# NixieClockControllerWemos.net
KiCad netlist of a schematic drawn in EAGLE
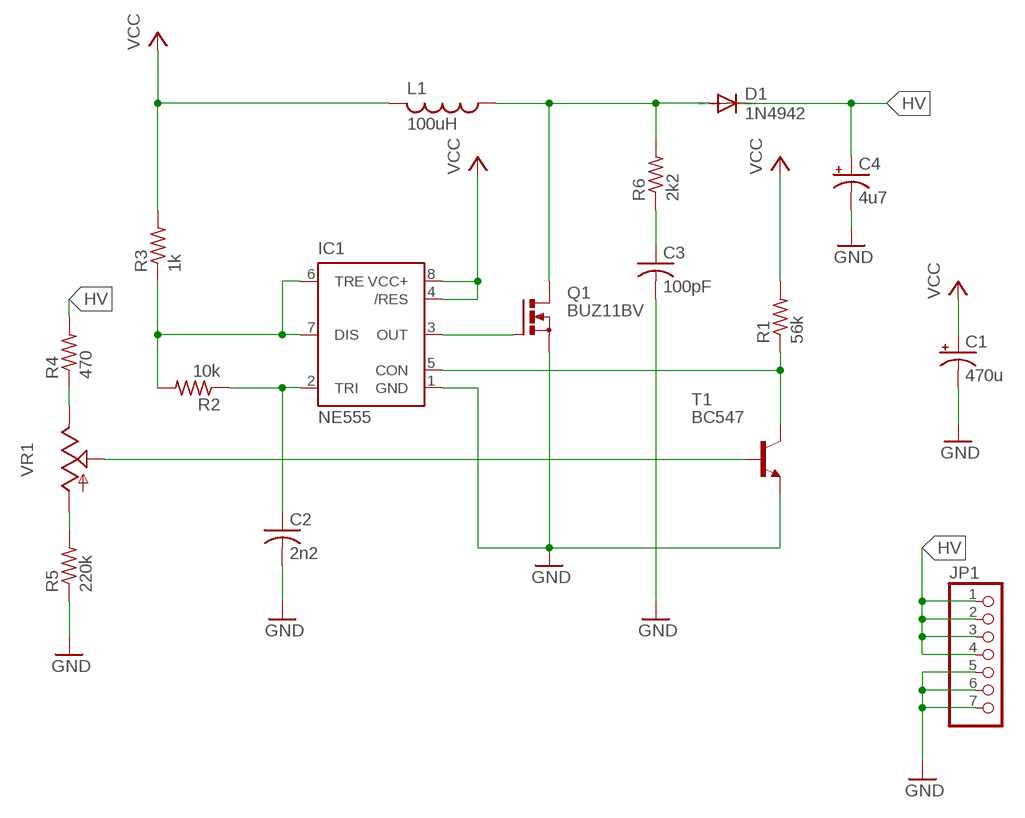
[diagram p0: schematic, sheet 1]
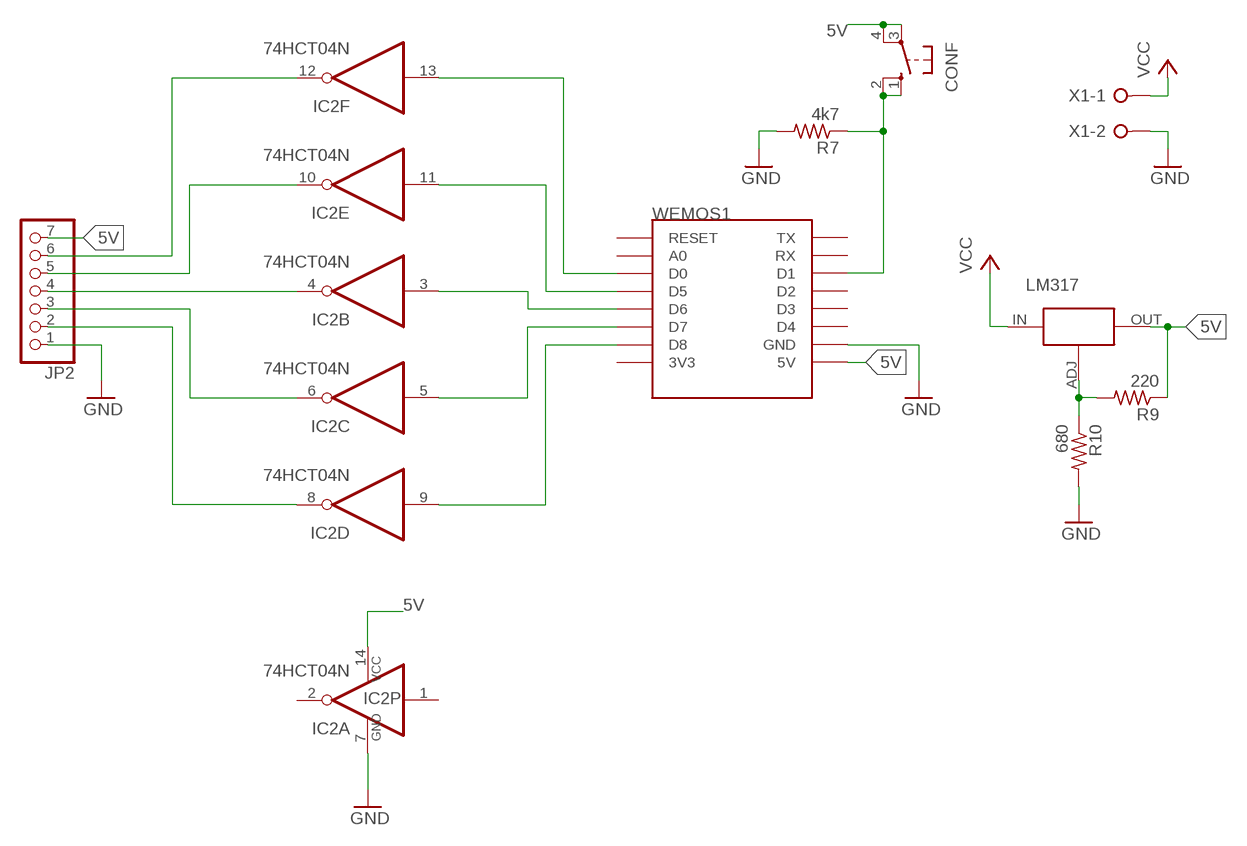
[diagram p1: schematic, sheet 2]

(export (version "E")
  (design (tool "Eeschema 10.0.6"))
  (components
    (comp (ref "C1")
      (value "470u")
      (footprint "eagle-import:E5-13")
      (libsource (lib "eagle-import") (part "CPOL-USE5-13"))
    )
    (comp (ref "C2")
      (value "2n2")
      (footprint "eagle-import:C050-025X075")
      (libsource (lib "eagle-import") (part "C-US050-025X075"))
    )
    (comp (ref "C3")
      (value "100pF")
      (footprint "eagle-import:C050-025X075")
      (libsource (lib "eagle-import") (part "C-US050-025X075"))
    )
    (comp (ref "C4")
      (value "4u7")
      (footprint "eagle-import:E3,5-8")
      (libsource (lib "eagle-import") (part "CPOL-USE3.5-8"))
    )
    (comp (ref "D1")
      (value "1N4942")
      (footprint "eagle-import:DO41-10")
      (libsource (lib "eagle-import") (part "1N4942"))
    )
    (comp (ref "IC1")
      (value "NE555")
      (footprint "eagle-import:DIL-08")
      (fields (field (name "MF") "Arrow Electronics") (field (name "MPN") "NE555N"))
      (libsource (lib "eagle-import") (part "NE555"))
    )
    (comp (ref "JP1")
      (value "PINHD-1X7")
      (footprint "eagle-import:1X07")
      (libsource (lib "eagle-import") (part "PINHD-1X7"))
    )
    (comp (ref "L1")
      (value "100uH")
      (footprint "eagle-import:RLB0914")
      (libsource (lib "eagle-import") (part "L-US"))
    )
    (comp (ref "Q1")
      (value "BUZ11BV")
      (footprint "eagle-import:TO220BV")
      (libsource (lib "eagle-import") (part "BUZ11BV"))
    )
    (comp (ref "R1")
      (value "56k")
      (footprint "eagle-import:0207_10")
      (libsource (lib "eagle-import") (part "R-US_0207/10"))
    )
    (comp (ref "R2")
      (value "10k")
      (footprint "eagle-import:0207_10")
      (libsource (lib "eagle-import") (part "R-US_0207/10"))
    )
    (comp (ref "R3")
      (value "1k")
      (footprint "eagle-import:0207_10")
      (libsource (lib "eagle-import") (part "R-US_0207/10"))
    )
    (comp (ref "R4")
      (value "470")
      (footprint "eagle-import:0207_10")
      (libsource (lib "eagle-import") (part "R-US_0207/10"))
    )
    (comp (ref "R5")
      (value "220k")
      (footprint "eagle-import:0207_10")
      (libsource (lib "eagle-import") (part "R-US_0207/10"))
    )
    (comp (ref "R6")
      (value "2k2")
      (footprint "eagle-import:0207_10")
      (libsource (lib "eagle-import") (part "R-US_0207/10"))
    )
    (comp (ref "T1")
      (value "BC547")
      (footprint "eagle-import:TO92")
      (libsource (lib "eagle-import") (part "BC547"))
    )
    (comp (ref "VR1")
      (value "TRIM_US-B25P")
      (footprint "eagle-import:B25P")
      (libsource (lib "eagle-import") (part "TRIM_US-B25P"))
    )
    (comp (ref "CONF")
      (value "10-XX")
      (footprint "eagle-import:B3F-10XX")
      (fields (field (name "MPN") "B3F-1000"))
      (libsource (lib "eagle-import") (part "10-XX"))
    )
    (comp (ref "IC2")
      (value "74HCT04N")
      (footprint "eagle-import:DIL14")
      (libsource (lib "eagle-import") (part "7404NHCT"))
    )
    (comp (ref "JP2")
      (value "PINHD-1X7")
      (footprint "eagle-import:1X07")
      (libsource (lib "eagle-import") (part "PINHD-1X7"))
    )
    (comp (ref "R7")
      (value "4k7")
      (footprint "eagle-import:0207_10")
      (libsource (lib "eagle-import") (part "R-US_0207/10"))
    )
    (comp (ref "R9")
      (value "220")
      (footprint "eagle-import:0207_10")
      (libsource (lib "eagle-import") (part "R-US_0207/10"))
    )
    (comp (ref "R10")
      (value "680")
      (footprint "eagle-import:0207_10")
      (libsource (lib "eagle-import") (part "R-US_0207/10"))
    )
    (comp (ref "U$3")
      (value "LM317-TO220")
      (footprint "eagle-import:LM317-TO220AV")
      (libsource (lib "eagle-import") (part "LM317-TO220"))
    )
    (comp (ref "WEMOS1")
      (value "WEMOS-D1-MINI")
      (footprint "eagle-import:WEMOS-D1-MINI")
      (libsource (lib "eagle-import") (part "WEMOS-D1-MINI"))
    )
    (comp (ref "X1")
      (value "W237-02P")
      (footprint "eagle-import:W237-132")
      (libsource (lib "eagle-import") (part "W237-02P"))
    )
  )
  (nets
    (net (code "1") (name "5V") (class "Default")
      (node (ref "CONF") (pin "3") (pinfunction "P_3") (pintype "passive"))
      (node (ref "CONF") (pin "4") (pinfunction "P1_4") (pintype "passive"))
      (node (ref "IC2") (pin "14") (pinfunction "VCC_14") (pintype "power_in"))
      (node (ref "JP2") (pin "7") (pinfunction "7_7") (pintype "passive"))
      (node (ref "R9") (pin "1") (pinfunction "1_1") (pintype "passive"))
      (node (ref "U$3") (pin "OUT") (pinfunction "VO_OUT") (pintype "output"))
      (node (ref "WEMOS1") (pin "5V") (pinfunction "5V_5V") (pintype "bidirectional"))
    )
    (net (code "2") (name "GND") (class "Default")
      (node (ref "C1") (pin "-") (pinfunction "-_-") (pintype "passive"))
      (node (ref "C2") (pin "2") (pinfunction "2_2") (pintype "passive"))
      (node (ref "C3") (pin "2") (pinfunction "2_2") (pintype "passive"))
      (node (ref "C4") (pin "-") (pinfunction "-_-") (pintype "passive"))
      (node (ref "IC1") (pin "1") (pinfunction "GND_1") (pintype "power_in"))
      (node (ref "IC2") (pin "7") (pinfunction "GND_7") (pintype "power_in"))
      (node (ref "JP1") (pin "5") (pinfunction "5_5") (pintype "passive"))
      (node (ref "JP1") (pin "6") (pinfunction "6_6") (pintype "passive"))
      (node (ref "JP1") (pin "7") (pinfunction "7_7") (pintype "passive"))
      (node (ref "JP2") (pin "1") (pinfunction "1_1") (pintype "passive"))
      (node (ref "Q1") (pin "S") (pinfunction "S_S") (pintype "passive"))
      (node (ref "R10") (pin "2") (pinfunction "2_2") (pintype "passive"))
      (node (ref "R5") (pin "1") (pinfunction "1_1") (pintype "passive"))
      (node (ref "R7") (pin "2") (pinfunction "2_2") (pintype "passive"))
      (node (ref "T1") (pin "1") (pinfunction "E_1") (pintype "passive"))
      (node (ref "WEMOS1") (pin "GND") (pinfunction "GND_GND") (pintype "bidirectional"))
      (node (ref "X1") (pin "2") (pinfunction "KL_2") (pintype "passive"))
    )
    (net (code "3") (name "HV") (class "Default")
      (node (ref "C4") (pin "+") (pinfunction "+_+") (pintype "passive"))
      (node (ref "D1") (pin "C") (pinfunction "C_C") (pintype "passive"))
      (node (ref "JP1") (pin "1") (pinfunction "1_1") (pintype "passive"))
      (node (ref "JP1") (pin "2") (pinfunction "2_2") (pintype "passive"))
      (node (ref "JP1") (pin "3") (pinfunction "3_3") (pintype "passive"))
      (node (ref "JP1") (pin "4") (pinfunction "4_4") (pintype "passive"))
      (node (ref "R4") (pin "2") (pinfunction "2_2") (pintype "passive"))
    )
    (net (code "4") (name "Net-(C3-Pad1)") (class "Default")
      (node (ref "C3") (pin "1") (pinfunction "1_1") (pintype "passive"))
      (node (ref "R6") (pin "1") (pinfunction "1_1") (pintype "passive"))
    )
    (net (code "5") (name "Net-(CONF-S)") (class "Default")
      (node (ref "CONF") (pin "1") (pinfunction "S_1") (pintype "passive"))
      (node (ref "CONF") (pin "2") (pinfunction "S1_2") (pintype "passive"))
      (node (ref "R7") (pin "1") (pinfunction "1_1") (pintype "passive"))
      (node (ref "WEMOS1") (pin "D1") (pinfunction "D1_D1") (pintype "bidirectional"))
    )
    (net (code "6") (name "Net-(D1-PadA)") (class "Default")
      (node (ref "D1") (pin "A") (pinfunction "A_A") (pintype "passive"))
      (node (ref "L1") (pin "1") (pinfunction "1_1") (pintype "passive"))
      (node (ref "Q1") (pin "D") (pinfunction "D_D") (pintype "passive"))
      (node (ref "R6") (pin "2") (pinfunction "2_2") (pintype "passive"))
    )
    (net (code "7") (name "Net-(IC1-CON)") (class "Default")
      (node (ref "IC1") (pin "5") (pinfunction "CON_5") (pintype "input"))
      (node (ref "R1") (pin "1") (pinfunction "1_1") (pintype "passive"))
      (node (ref "T1") (pin "3") (pinfunction "C_3") (pintype "passive"))
    )
    (net (code "8") (name "Net-(IC1-DIS)") (class "Default")
      (node (ref "IC1") (pin "6") (pinfunction "TRE_6") (pintype "input"))
      (node (ref "IC1") (pin "7") (pinfunction "DIS_7") (pintype "input"))
      (node (ref "R2") (pin "2") (pinfunction "2_2") (pintype "passive"))
      (node (ref "R3") (pin "1") (pinfunction "1_1") (pintype "passive"))
    )
    (net (code "9") (name "Net-(IC1-OUT)") (class "Default")
      (node (ref "IC1") (pin "3") (pinfunction "OUT_3") (pintype "output"))
      (node (ref "Q1") (pin "G") (pinfunction "G_G") (pintype "passive"))
    )
    (net (code "10") (name "Net-(IC1-TRI)") (class "Default")
      (node (ref "C2") (pin "1") (pinfunction "1_1") (pintype "passive"))
      (node (ref "IC1") (pin "2") (pinfunction "TRI_2") (pintype "input"))
      (node (ref "R2") (pin "1") (pinfunction "1_1") (pintype "passive"))
    )
    (net (code "11") (name "Net-(IC2B-I)") (class "Default")
      (node (ref "IC2") (pin "3") (pinfunction "I_3") (pintype "input"))
      (node (ref "WEMOS1") (pin "D6") (pinfunction "D6_D6") (pintype "bidirectional"))
    )
    (net (code "12") (name "Net-(IC2B-O)") (class "Default")
      (node (ref "IC2") (pin "4") (pinfunction "O_4") (pintype "output"))
      (node (ref "JP2") (pin "4") (pinfunction "4_4") (pintype "passive"))
    )
    (net (code "13") (name "Net-(IC2C-I)") (class "Default")
      (node (ref "IC2") (pin "5") (pinfunction "I_5") (pintype "input"))
      (node (ref "WEMOS1") (pin "D7") (pinfunction "D7_D7") (pintype "bidirectional"))
    )
    (net (code "14") (name "Net-(IC2C-O)") (class "Default")
      (node (ref "IC2") (pin "6") (pinfunction "O_6") (pintype "output"))
      (node (ref "JP2") (pin "3") (pinfunction "3_3") (pintype "passive"))
    )
    (net (code "15") (name "Net-(IC2D-I)") (class "Default")
      (node (ref "IC2") (pin "9") (pinfunction "I_9") (pintype "input"))
      (node (ref "WEMOS1") (pin "D8") (pinfunction "D8_D8") (pintype "bidirectional"))
    )
    (net (code "16") (name "Net-(IC2D-O)") (class "Default")
      (node (ref "IC2") (pin "8") (pinfunction "O_8") (pintype "output"))
      (node (ref "JP2") (pin "2") (pinfunction "2_2") (pintype "passive"))
    )
    (net (code "17") (name "Net-(IC2E-I)") (class "Default")
      (node (ref "IC2") (pin "11") (pinfunction "I_11") (pintype "input"))
      (node (ref "WEMOS1") (pin "D5") (pinfunction "D5_D5") (pintype "bidirectional"))
    )
    (net (code "18") (name "Net-(IC2E-O)") (class "Default")
      (node (ref "IC2") (pin "10") (pinfunction "O_10") (pintype "output"))
      (node (ref "JP2") (pin "5") (pinfunction "5_5") (pintype "passive"))
    )
    (net (code "19") (name "Net-(IC2F-I)") (class "Default")
      (node (ref "IC2") (pin "13") (pinfunction "I_13") (pintype "input"))
      (node (ref "WEMOS1") (pin "D0") (pinfunction "D0_D0") (pintype "bidirectional"))
    )
    (net (code "20") (name "Net-(IC2F-O)") (class "Default")
      (node (ref "IC2") (pin "12") (pinfunction "O_12") (pintype "output"))
      (node (ref "JP2") (pin "6") (pinfunction "6_6") (pintype "passive"))
    )
    (net (code "21") (name "Net-(R4-Pad1)") (class "Default")
      (node (ref "R4") (pin "1") (pinfunction "1_1") (pintype "passive"))
      (node (ref "VR1") (pin "E") (pinfunction "E_E") (pintype "passive"))
    )
    (net (code "22") (name "Net-(R5-Pad2)") (class "Default")
      (node (ref "R5") (pin "2") (pinfunction "2_2") (pintype "passive"))
      (node (ref "VR1") (pin "A") (pinfunction "A_A") (pintype "passive"))
    )
    (net (code "23") (name "Net-(R10-Pad1)") (class "Default")
      (node (ref "R10") (pin "1") (pinfunction "1_1") (pintype "passive"))
      (node (ref "R9") (pin "2") (pinfunction "2_2") (pintype "passive"))
      (node (ref "U$3") (pin "ADJ") (pinfunction "ADJ_ADJ") (pintype "power_in"))
    )
    (net (code "24") (name "Net-(T1-B)") (class "Default")
      (node (ref "T1") (pin "2") (pinfunction "B_2") (pintype "passive"))
      (node (ref "VR1") (pin "S") (pinfunction "S_S") (pintype "passive"))
    )
    (net (code "25") (name "VCC") (class "Default")
      (node (ref "C1") (pin "+") (pinfunction "+_+") (pintype "passive"))
      (node (ref "IC1") (pin "4") (pinfunction "/RES_4") (pintype "input"))
      (node (ref "IC1") (pin "8") (pinfunction "VCC+_8") (pintype "power_in"))
      (node (ref "L1") (pin "2") (pinfunction "2_2") (pintype "passive"))
      (node (ref "R1") (pin "2") (pinfunction "2_2") (pintype "passive"))
      (node (ref "R3") (pin "2") (pinfunction "2_2") (pintype "passive"))
      (node (ref "U$3") (pin "IN") (pinfunction "VI_IN") (pintype "input"))
      (node (ref "X1") (pin "1") (pinfunction "KL_1") (pintype "passive"))
    )
    (net (code "26") (name "unconnected-(IC2A-I-Pad1)") (class "Default")
      (node (ref "IC2") (pin "1") (pinfunction "I_1") (pintype "input"))
    )
    (net (code "27") (name "unconnected-(IC2A-O-Pad2)") (class "Default")
      (node (ref "IC2") (pin "2") (pinfunction "O_2") (pintype "output"))
    )
    (net (code "28") (name "unconnected-(WEMOS1-Pad3V3)") (class "Default")
      (node (ref "WEMOS1") (pin "3V3") (pinfunction "3V3_3V3") (pintype "bidirectional"))
    )
    (net (code "29") (name "unconnected-(WEMOS1-PadA0)") (class "Default")
      (node (ref "WEMOS1") (pin "A0") (pinfunction "A0_A0") (pintype "bidirectional"))
    )
    (net (code "30") (name "unconnected-(WEMOS1-PadD2)") (class "Default")
      (node (ref "WEMOS1") (pin "D2") (pinfunction "D2_D2") (pintype "bidirectional"))
    )
    (net (code "31") (name "unconnected-(WEMOS1-PadD3)") (class "Default")
      (node (ref "WEMOS1") (pin "D3") (pinfunction "D3_D3") (pintype "bidirectional"))
    )
    (net (code "32") (name "unconnected-(WEMOS1-PadD4)") (class "Default")
      (node (ref "WEMOS1") (pin "D4") (pinfunction "D4_D4") (pintype "bidirectional"))
    )
    (net (code "33") (name "unconnected-(WEMOS1-PadRESET)") (class "Default")
      (node (ref "WEMOS1") (pin "RESET") (pinfunction "RESET_RESET") (pintype "bidirectional"))
    )
    (net (code "34") (name "unconnected-(WEMOS1-PadRX)") (class "Default")
      (node (ref "WEMOS1") (pin "RX") (pinfunction "RX_RX") (pintype "bidirectional"))
    )
    (net (code "35") (name "unconnected-(WEMOS1-PadTX)") (class "Default")
      (node (ref "WEMOS1") (pin "TX") (pinfunction "TX_TX") (pintype "bidirectional"))
    )
  )
)
